# singleHbridge-v1.net
KiCad netlist of a schematic drawn in EAGLE
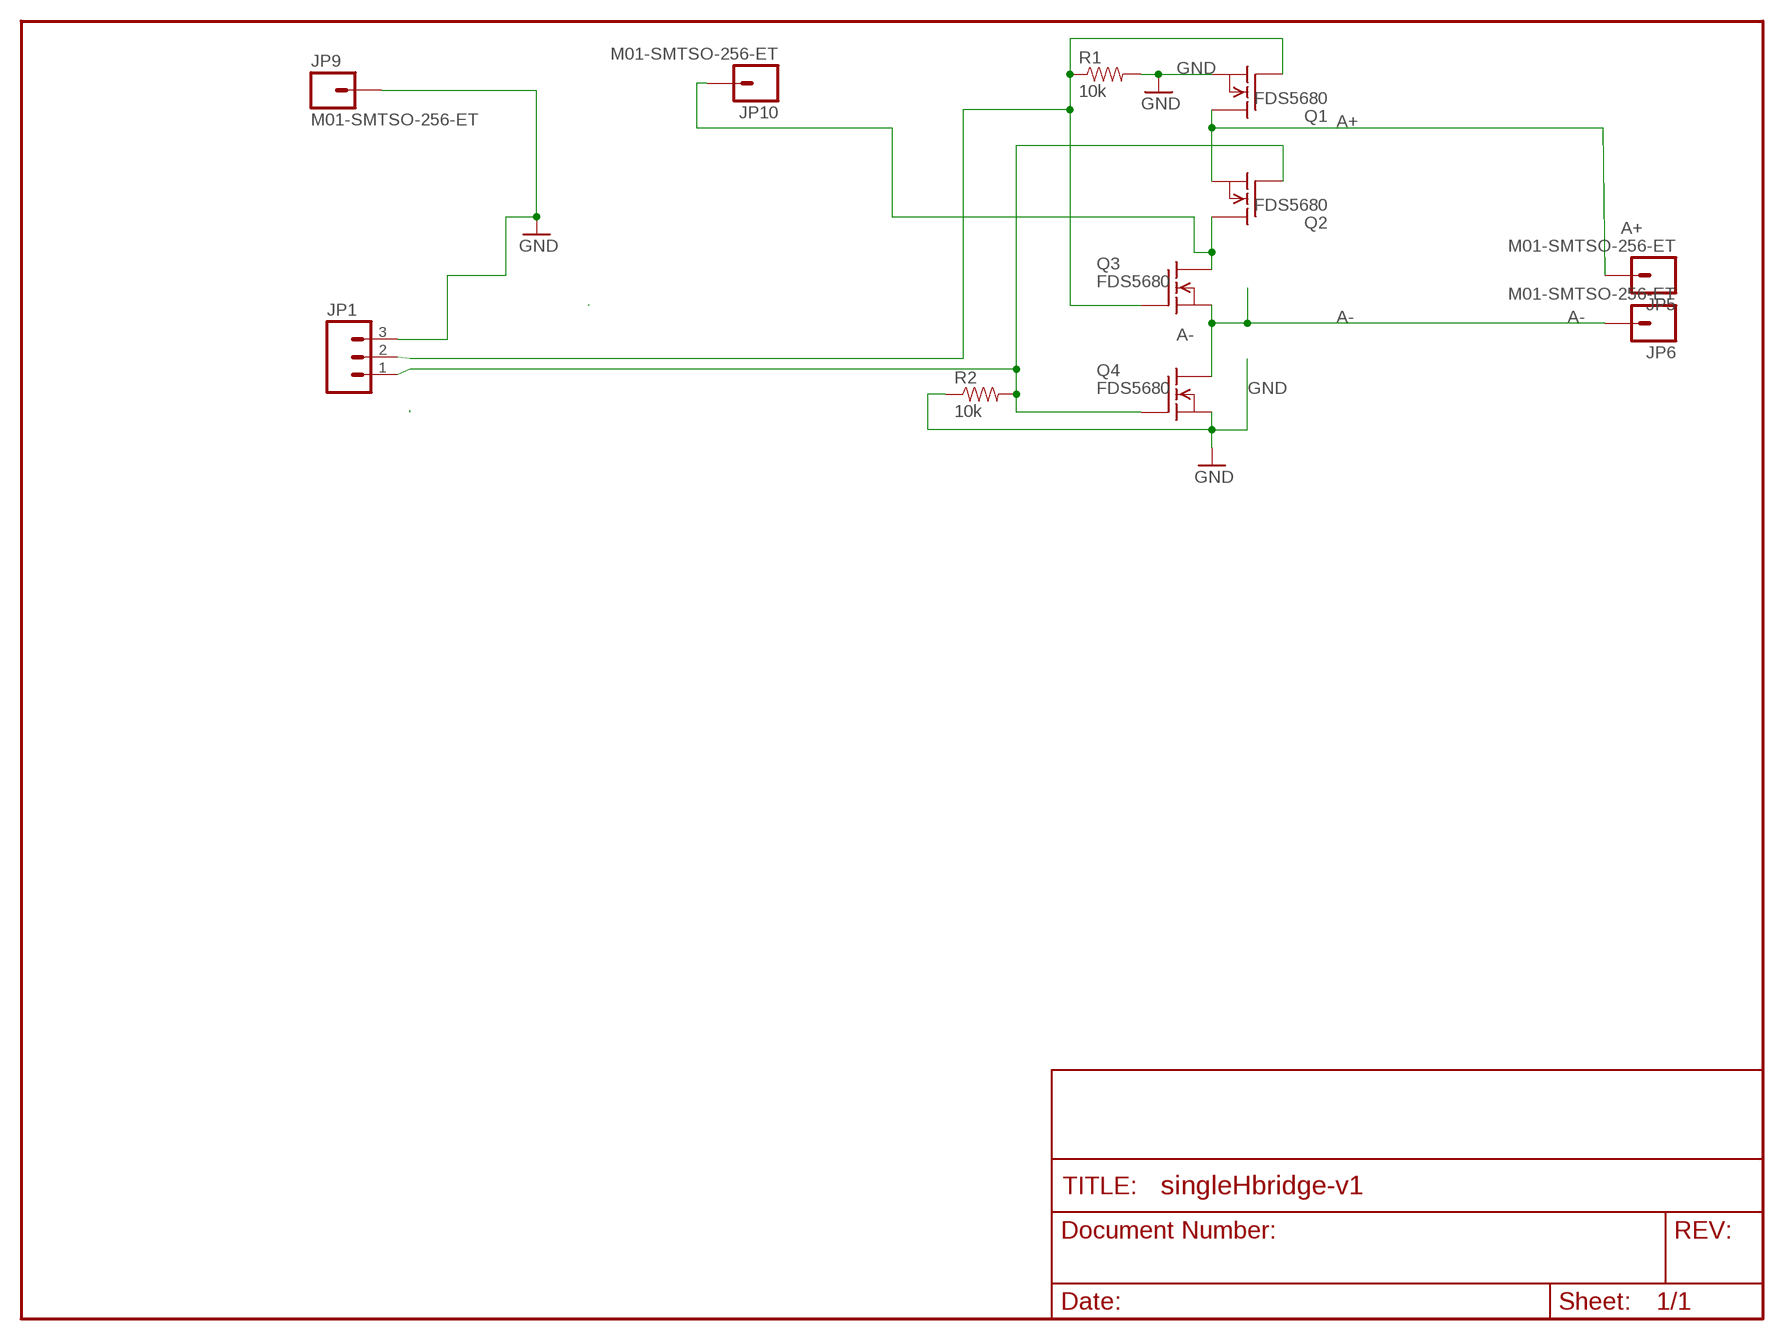
[diagram p0: schematic, sheet 1]

(export (version "E")
  (design (tool "Eeschema 10.0.6"))
  (components
    (comp (ref "JP1")
      (value "M03PTH")
      (footprint "eagle-import:1X03")
      (libsource (lib "eagle-import") (part "M03PTH"))
    )
    (comp (ref "JP5")
      (value "M01-SMTSO-256-ET")
      (footprint "eagle-import:SMTSO-256-ET")
      (libsource (lib "eagle-import") (part "M01-SMTSO-256-ET"))
    )
    (comp (ref "JP6")
      (value "M01-SMTSO-256-ET")
      (footprint "eagle-import:SMTSO-256-ET")
      (libsource (lib "eagle-import") (part "M01-SMTSO-256-ET"))
    )
    (comp (ref "JP9")
      (value "M01-SMTSO-256-ET")
      (footprint "eagle-import:SMTSO-256-ET")
      (libsource (lib "eagle-import") (part "M01-SMTSO-256-ET"))
    )
    (comp (ref "JP10")
      (value "M01-SMTSO-256-ET")
      (footprint "eagle-import:SMTSO-256-ET")
      (libsource (lib "eagle-import") (part "M01-SMTSO-256-ET"))
    )
    (comp (ref "Q1")
      (value "FDS5680")
      (footprint "eagle-import:SO-8")
      (libsource (lib "eagle-import") (part "FDS5680"))
    )
    (comp (ref "Q2")
      (value "FDS5680")
      (footprint "eagle-import:SO-8")
      (libsource (lib "eagle-import") (part "FDS5680"))
    )
    (comp (ref "Q3")
      (value "FDS5680")
      (footprint "eagle-import:SO-8")
      (libsource (lib "eagle-import") (part "FDS5680"))
    )
    (comp (ref "Q4")
      (value "FDS5680")
      (footprint "eagle-import:SO-8")
      (libsource (lib "eagle-import") (part "FDS5680"))
    )
    (comp (ref "R1")
      (value "10k")
      (footprint "eagle-import:0603-RES")
      (libsource (lib "eagle-import") (part "RESISTOR0603-RES"))
    )
    (comp (ref "R2")
      (value "10k")
      (footprint "eagle-import:0603-RES")
      (libsource (lib "eagle-import") (part "RESISTOR0603-RES"))
    )
  )
  (nets
    (net (code "1") (name "/A+") (class "Default")
      (node (ref "JP5") (pin "P$1") (pinfunction "1_P$1") (pintype "passive"))
      (node (ref "Q1") (pin "5") (pinfunction "D_5") (pintype "passive"))
      (node (ref "Q1") (pin "6") (pinfunction "D_6") (pintype "passive"))
      (node (ref "Q1") (pin "7") (pinfunction "D_7") (pintype "passive"))
      (node (ref "Q1") (pin "8") (pinfunction "D_8") (pintype "passive"))
      (node (ref "Q2") (pin "1") (pinfunction "S_1") (pintype "passive"))
      (node (ref "Q2") (pin "2") (pinfunction "S_2") (pintype "passive"))
      (node (ref "Q2") (pin "3") (pinfunction "S_3") (pintype "passive"))
    )
    (net (code "2") (name "/A-") (class "Default")
      (node (ref "JP6") (pin "P$1") (pinfunction "1_P$1") (pintype "passive"))
      (node (ref "Q3") (pin "1") (pinfunction "S_1") (pintype "passive"))
      (node (ref "Q3") (pin "2") (pinfunction "S_2") (pintype "passive"))
      (node (ref "Q3") (pin "3") (pinfunction "S_3") (pintype "passive"))
      (node (ref "Q4") (pin "5") (pinfunction "D_5") (pintype "passive"))
      (node (ref "Q4") (pin "6") (pinfunction "D_6") (pintype "passive"))
      (node (ref "Q4") (pin "7") (pinfunction "D_7") (pintype "passive"))
      (node (ref "Q4") (pin "8") (pinfunction "D_8") (pintype "passive"))
    )
    (net (code "3") (name "GND") (class "Default")
      (node (ref "JP1") (pin "3") (pinfunction "3_3") (pintype "passive"))
      (node (ref "JP9") (pin "P$1") (pinfunction "1_P$1") (pintype "passive"))
      (node (ref "Q1") (pin "1") (pinfunction "S_1") (pintype "passive"))
      (node (ref "Q1") (pin "2") (pinfunction "S_2") (pintype "passive"))
      (node (ref "Q1") (pin "3") (pinfunction "S_3") (pintype "passive"))
      (node (ref "Q4") (pin "1") (pinfunction "S_1") (pintype "passive"))
      (node (ref "Q4") (pin "2") (pinfunction "S_2") (pintype "passive"))
      (node (ref "Q4") (pin "3") (pinfunction "S_3") (pintype "passive"))
      (node (ref "R1") (pin "2") (pinfunction "2_2") (pintype "passive"))
      (node (ref "R2") (pin "1") (pinfunction "1_1") (pintype "passive"))
    )
    (net (code "4") (name "Net-(JP10-1)") (class "Default")
      (node (ref "JP10") (pin "P$1") (pinfunction "1_P$1") (pintype "passive"))
      (node (ref "Q2") (pin "5") (pinfunction "D_5") (pintype "passive"))
      (node (ref "Q2") (pin "6") (pinfunction "D_6") (pintype "passive"))
      (node (ref "Q2") (pin "7") (pinfunction "D_7") (pintype "passive"))
      (node (ref "Q2") (pin "8") (pinfunction "D_8") (pintype "passive"))
      (node (ref "Q3") (pin "5") (pinfunction "D_5") (pintype "passive"))
      (node (ref "Q3") (pin "6") (pinfunction "D_6") (pintype "passive"))
      (node (ref "Q3") (pin "7") (pinfunction "D_7") (pintype "passive"))
      (node (ref "Q3") (pin "8") (pinfunction "D_8") (pintype "passive"))
    )
    (net (code "5") (name "Net-(Q1-G)") (class "Default")
      (node (ref "JP1") (pin "2") (pinfunction "2_2") (pintype "passive"))
      (node (ref "Q1") (pin "4") (pinfunction "G_4") (pintype "passive"))
      (node (ref "Q3") (pin "4") (pinfunction "G_4") (pintype "passive"))
      (node (ref "R1") (pin "1") (pinfunction "1_1") (pintype "passive"))
    )
    (net (code "6") (name "Net-(Q2-G)") (class "Default")
      (node (ref "JP1") (pin "1") (pinfunction "1_1") (pintype "passive"))
      (node (ref "Q2") (pin "4") (pinfunction "G_4") (pintype "passive"))
      (node (ref "Q4") (pin "4") (pinfunction "G_4") (pintype "passive"))
      (node (ref "R2") (pin "2") (pinfunction "2_2") (pintype "passive"))
    )
  )
)
